# Pallette_v0_5.net
KiCad netlist of a schematic drawn in Altium Designer
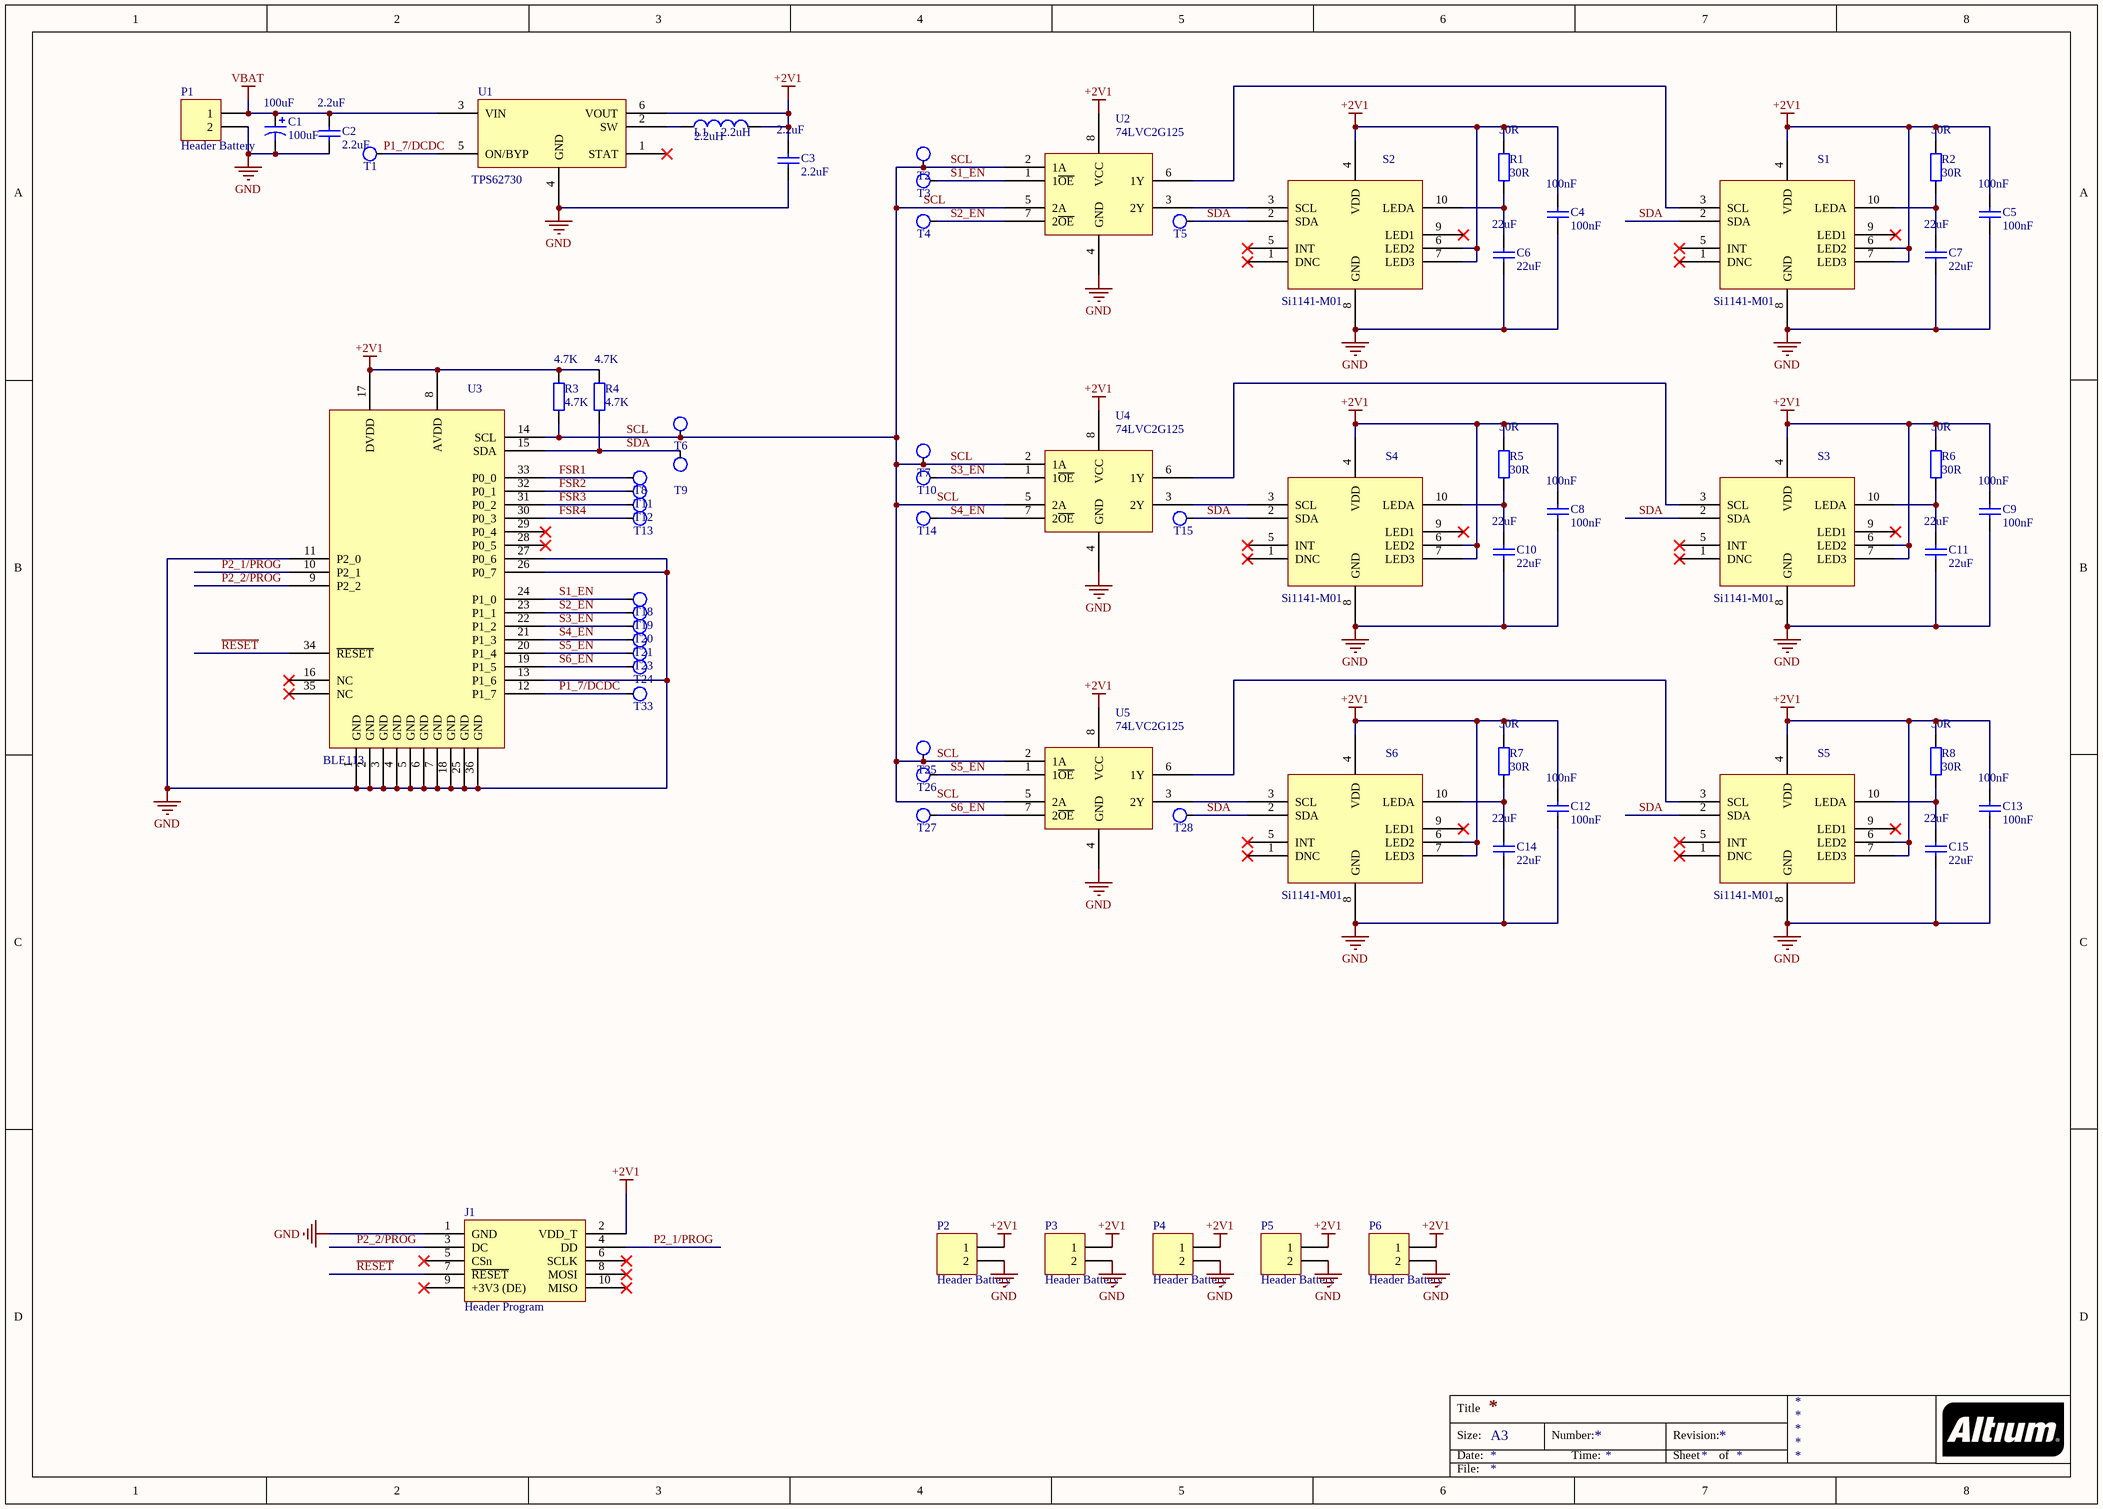
[diagram p0: Pallette v0.5.SchDoc]

(export (version "E")
  (design (tool "Eeschema 10.0.6"))
  (components
    (comp (ref "C1")
      (value "100uF")
      (footprint "1411")
      (description "CAP TANT POLY 100UF 8V 1411")
      (fields
        (field (name "ALTIUM_VALUE") "100uF")
        (field (name "DIGI-KEY PART NUMBER") "P16641CT-ND")
        (field (name "MANUFACTURER") "Panasonic Electronic Components")
      )
      (libsource (lib "Schlib") (part "Cap Pol 100uF"))
    )
    (comp (ref "C2")
      (value "2.2uF")
      (footprint "0402")
      (description "CAP CER 2.2UF 6.3V X5R 0402")
      (fields
        (field (name "ALTIUM_VALUE") "2.2uF")
        (field (name "DIGI-KEY PART NUMBER") "478-7885-1-ND")
        (field (name "MANUFACTURER PART NUMBER") "04026D225KAT2A")
      )
      (libsource (lib "Schlib") (part "Cap 2.2uF"))
    )
    (comp (ref "C3")
      (value "2.2uF")
      (footprint "0402")
      (description "CAP CER 2.2UF 6.3V X5R 0402")
      (fields
        (field (name "ALTIUM_VALUE") "2.2uF")
        (field (name "DIGI-KEY PART NUMBER") "478-7885-1-ND")
        (field (name "MANUFACTURER PART NUMBER") "04026D225KAT2A")
      )
      (libsource (lib "Schlib") (part "Cap 2.2uF"))
    )
    (comp (ref "C4")
      (value "100nF")
      (footprint "0402")
      (description "CAP CER 0.1UF 10V X5R 0402")
      (fields
        (field (name "ALTIUM_VALUE") "100nF")
        (field (name "DIGI-KEY PART NUMBER") "490-1318-1-ND")
        (field (name "MANUFACTURER") "Murata")
      )
      (libsource (lib "Schlib") (part "Cap 100nF"))
    )
    (comp (ref "C5")
      (value "100nF")
      (footprint "0402")
      (description "CAP CER 0.1UF 10V X5R 0402")
      (fields
        (field (name "ALTIUM_VALUE") "100nF")
        (field (name "DIGI-KEY PART NUMBER") "490-1318-1-ND")
        (field (name "MANUFACTURER") "Murata")
      )
      (libsource (lib "Schlib") (part "Cap 100nF"))
    )
    (comp (ref "C6")
      (value "22uF")
      (footprint "0603")
      (description "CAP CER 22UF 6.3V X5R 0603")
      (fields
        (field (name "ALTIUM_VALUE") "22uF")
        (field (name "DIGI-KEY PART NUMBER") "490-7611-1-ND")
        (field (name "MANUFACTURER PART NUMBER") "GRM188R60J226MEA0D")
      )
      (libsource (lib "Schlib") (part "Cap 22uF"))
    )
    (comp (ref "C7")
      (value "22uF")
      (footprint "0603")
      (description "CAP CER 22UF 6.3V X5R 0603")
      (fields
        (field (name "ALTIUM_VALUE") "22uF")
        (field (name "DIGI-KEY PART NUMBER") "490-7611-1-ND")
        (field (name "MANUFACTURER PART NUMBER") "GRM188R60J226MEA0D")
      )
      (libsource (lib "Schlib") (part "Cap 22uF"))
    )
    (comp (ref "C8")
      (value "100nF")
      (footprint "0402")
      (description "CAP CER 0.1UF 10V X5R 0402")
      (fields
        (field (name "ALTIUM_VALUE") "100nF")
        (field (name "DIGI-KEY PART NUMBER") "490-1318-1-ND")
        (field (name "MANUFACTURER") "Murata")
      )
      (libsource (lib "Schlib") (part "Cap 100nF"))
    )
    (comp (ref "C9")
      (value "100nF")
      (footprint "0402")
      (description "CAP CER 0.1UF 10V X5R 0402")
      (fields
        (field (name "ALTIUM_VALUE") "100nF")
        (field (name "DIGI-KEY PART NUMBER") "490-1318-1-ND")
        (field (name "MANUFACTURER") "Murata")
      )
      (libsource (lib "Schlib") (part "Cap 100nF"))
    )
    (comp (ref "C10")
      (value "22uF")
      (footprint "0603")
      (description "CAP CER 22UF 6.3V X5R 0603")
      (fields
        (field (name "ALTIUM_VALUE") "22uF")
        (field (name "DIGI-KEY PART NUMBER") "490-7611-1-ND")
        (field (name "MANUFACTURER PART NUMBER") "GRM188R60J226MEA0D")
      )
      (libsource (lib "Schlib") (part "Cap 22uF"))
    )
    (comp (ref "C11")
      (value "22uF")
      (footprint "0603")
      (description "CAP CER 22UF 6.3V X5R 0603")
      (fields
        (field (name "ALTIUM_VALUE") "22uF")
        (field (name "DIGI-KEY PART NUMBER") "490-7611-1-ND")
        (field (name "MANUFACTURER PART NUMBER") "GRM188R60J226MEA0D")
      )
      (libsource (lib "Schlib") (part "Cap 22uF"))
    )
    (comp (ref "C12")
      (value "100nF")
      (footprint "0402")
      (description "CAP CER 0.1UF 10V X5R 0402")
      (fields
        (field (name "ALTIUM_VALUE") "100nF")
        (field (name "DIGI-KEY PART NUMBER") "490-1318-1-ND")
        (field (name "MANUFACTURER") "Murata")
      )
      (libsource (lib "Schlib") (part "Cap 100nF"))
    )
    (comp (ref "C13")
      (value "100nF")
      (footprint "0402")
      (description "CAP CER 0.1UF 10V X5R 0402")
      (fields
        (field (name "ALTIUM_VALUE") "100nF")
        (field (name "DIGI-KEY PART NUMBER") "490-1318-1-ND")
        (field (name "MANUFACTURER") "Murata")
      )
      (libsource (lib "Schlib") (part "Cap 100nF"))
    )
    (comp (ref "C14")
      (value "22uF")
      (footprint "0603")
      (description "CAP CER 22UF 6.3V X5R 0603")
      (fields
        (field (name "ALTIUM_VALUE") "22uF")
        (field (name "DIGI-KEY PART NUMBER") "490-7611-1-ND")
        (field (name "MANUFACTURER PART NUMBER") "GRM188R60J226MEA0D")
      )
      (libsource (lib "Schlib") (part "Cap 22uF"))
    )
    (comp (ref "C15")
      (value "22uF")
      (footprint "0603")
      (description "CAP CER 22UF 6.3V X5R 0603")
      (fields
        (field (name "ALTIUM_VALUE") "22uF")
        (field (name "DIGI-KEY PART NUMBER") "490-7611-1-ND")
        (field (name "MANUFACTURER PART NUMBER") "GRM188R60J226MEA0D")
      )
      (libsource (lib "Schlib") (part "Cap 22uF"))
    )
    (comp (ref "J1")
      (value "Header Program")
      (footprint "TC2050-IDC-NL")
      (description "PADS PROGRAMMING")
      (libsource (lib "Schlib") (part "Header Program"))
    )
    (comp (ref "L1")
      (value "2.2uH")
      (footprint "0805")
      (description "FIXED IND 2.2UH 800MA 120 MOHM")
      (fields
        (field (name "ALTIUM_VALUE") "2.2uH")
        (field (name "DIGI-KEY PART NUMBER") "445-6758-1-ND")
        (field (name "MANUFACTURER") "TDK Corporation")
      )
      (libsource (lib "Schlib") (part "Ind 2.2uH"))
    )
    (comp (ref "P1")
      (value "Header Battery")
      (footprint "Battery Leads")
      (description "PADS BATTERY")
      (fields (field (name "PUBLISHER") "Altium Limited"))
      (libsource (lib "Schlib") (part "Header Battery"))
    )
    (comp (ref "P2")
      (value "Header Battery")
      (footprint "Battery Leads")
      (description "PADS BATTERY")
      (fields (field (name "PUBLISHER") "Altium Limited"))
      (libsource (lib "Schlib") (part "Header Battery"))
    )
    (comp (ref "P3")
      (value "Header Battery")
      (footprint "Battery Leads")
      (description "PADS BATTERY")
      (fields (field (name "PUBLISHER") "Altium Limited"))
      (libsource (lib "Schlib") (part "Header Battery"))
    )
    (comp (ref "P4")
      (value "Header Battery")
      (footprint "Battery Leads")
      (description "PADS BATTERY")
      (fields (field (name "PUBLISHER") "Altium Limited"))
      (libsource (lib "Schlib") (part "Header Battery"))
    )
    (comp (ref "P5")
      (value "Header Battery")
      (footprint "Battery Leads")
      (description "PADS BATTERY")
      (fields (field (name "PUBLISHER") "Altium Limited"))
      (libsource (lib "Schlib") (part "Header Battery"))
    )
    (comp (ref "P6")
      (value "Header Battery")
      (footprint "Battery Leads")
      (description "PADS BATTERY")
      (fields (field (name "PUBLISHER") "Altium Limited"))
      (libsource (lib "Schlib") (part "Header Battery"))
    )
    (comp (ref "R1")
      (value "30R")
      (footprint "0402")
      (description "RES SMD 30 OHM 1% 1/16W 0402")
      (fields
        (field (name "ALTIUM_VALUE") "30R")
        (field (name "DIGI-KEY PART NUMBER") "311-30LRCT-ND")
        (field (name "MANUFACTURER") "Yageo")
      )
      (libsource (lib "Schlib") (part "Res 30R"))
    )
    (comp (ref "R2")
      (value "30R")
      (footprint "0402")
      (description "RES SMD 30 OHM 1% 1/16W 0402")
      (fields
        (field (name "ALTIUM_VALUE") "30R")
        (field (name "DIGI-KEY PART NUMBER") "311-30LRCT-ND")
        (field (name "MANUFACTURER") "Yageo")
      )
      (libsource (lib "Schlib") (part "Res 30R"))
    )
    (comp (ref "R3")
      (value "4.7K")
      (footprint "0402")
      (description "RES SMD 4.7K OHM 1% 1/16W 0402")
      (fields
        (field (name "ALTIUM_VALUE") "4.7K")
        (field (name "DIGI-KEY PART NUMBER") "311-4.7KLRCT-ND")
        (field (name "MANUFACTURER") "Yageo")
      )
      (libsource (lib "Schlib") (part "Res 4.7K"))
    )
    (comp (ref "R4")
      (value "4.7K")
      (footprint "0402")
      (description "RES SMD 4.7K OHM 1% 1/16W 0402")
      (fields
        (field (name "ALTIUM_VALUE") "4.7K")
        (field (name "DIGI-KEY PART NUMBER") "311-4.7KLRCT-ND")
        (field (name "MANUFACTURER") "Yageo")
      )
      (libsource (lib "Schlib") (part "Res 4.7K"))
    )
    (comp (ref "R5")
      (value "30R")
      (footprint "0402")
      (description "RES SMD 30 OHM 1% 1/16W 0402")
      (fields
        (field (name "ALTIUM_VALUE") "30R")
        (field (name "DIGI-KEY PART NUMBER") "311-30LRCT-ND")
        (field (name "MANUFACTURER") "Yageo")
      )
      (libsource (lib "Schlib") (part "Res 30R"))
    )
    (comp (ref "R6")
      (value "30R")
      (footprint "0402")
      (description "RES SMD 30 OHM 1% 1/16W 0402")
      (fields
        (field (name "ALTIUM_VALUE") "30R")
        (field (name "DIGI-KEY PART NUMBER") "311-30LRCT-ND")
        (field (name "MANUFACTURER") "Yageo")
      )
      (libsource (lib "Schlib") (part "Res 30R"))
    )
    (comp (ref "R7")
      (value "30R")
      (footprint "0402")
      (description "RES SMD 30 OHM 1% 1/16W 0402")
      (fields
        (field (name "ALTIUM_VALUE") "30R")
        (field (name "DIGI-KEY PART NUMBER") "311-30LRCT-ND")
        (field (name "MANUFACTURER") "Yageo")
      )
      (libsource (lib "Schlib") (part "Res 30R"))
    )
    (comp (ref "R8")
      (value "30R")
      (footprint "0402")
      (description "RES SMD 30 OHM 1% 1/16W 0402")
      (fields
        (field (name "ALTIUM_VALUE") "30R")
        (field (name "DIGI-KEY PART NUMBER") "311-30LRCT-ND")
        (field (name "MANUFACTURER") "Yageo")
      )
      (libsource (lib "Schlib") (part "Res 30R"))
    )
    (comp (ref "S1")
      (value "Si1141-M01")
      (footprint "SI1141-M01")
      (description "SENSOR IR PROXIMITY AMB LT 10QFN")
      (fields
        (field (name "DIGI-KEY PART NUMBER") "336-3260-1-ND")
        (field (name "MANUFACTURER") "Silicon Labs")
      )
      (libsource (lib "Schlib") (part "Si1141-M01"))
    )
    (comp (ref "S2")
      (value "Si1141-M01")
      (footprint "SI1141-M01")
      (description "SENSOR IR PROXIMITY AMB LT 10QFN")
      (fields
        (field (name "DIGI-KEY PART NUMBER") "336-3260-1-ND")
        (field (name "MANUFACTURER") "Silicon Labs")
      )
      (libsource (lib "Schlib") (part "Si1141-M01"))
    )
    (comp (ref "S3")
      (value "Si1141-M01")
      (footprint "SI1141-M01")
      (description "SENSOR IR PROXIMITY AMB LT 10QFN")
      (fields
        (field (name "DIGI-KEY PART NUMBER") "336-3260-1-ND")
        (field (name "MANUFACTURER") "Silicon Labs")
      )
      (libsource (lib "Schlib") (part "Si1141-M01"))
    )
    (comp (ref "S4")
      (value "Si1141-M01")
      (footprint "SI1141-M01")
      (description "SENSOR IR PROXIMITY AMB LT 10QFN")
      (fields
        (field (name "DIGI-KEY PART NUMBER") "336-3260-1-ND")
        (field (name "MANUFACTURER") "Silicon Labs")
      )
      (libsource (lib "Schlib") (part "Si1141-M01"))
    )
    (comp (ref "S5")
      (value "Si1141-M01")
      (footprint "SI1141-M01")
      (description "SENSOR IR PROXIMITY AMB LT 10QFN")
      (fields
        (field (name "DIGI-KEY PART NUMBER") "336-3260-1-ND")
        (field (name "MANUFACTURER") "Silicon Labs")
      )
      (libsource (lib "Schlib") (part "Si1141-M01"))
    )
    (comp (ref "S6")
      (value "Si1141-M01")
      (footprint "SI1141-M01")
      (description "SENSOR IR PROXIMITY AMB LT 10QFN")
      (fields
        (field (name "DIGI-KEY PART NUMBER") "336-3260-1-ND")
        (field (name "MANUFACTURER") "Silicon Labs")
      )
      (libsource (lib "Schlib") (part "Si1141-M01"))
    )
    (comp (ref "T1")
      (value "TP 1.2X2MM")
      (footprint "TP 1.2x2MM")
      (description "TEST POINT")
      (libsource (lib "Schlib") (part "TP 1.2X2MM"))
    )
    (comp (ref "T2")
      (value "TP 1.2X2MM")
      (footprint "TP 1.2x2MM")
      (description "TEST POINT")
      (libsource (lib "Schlib") (part "TP 1.2X2MM"))
    )
    (comp (ref "T3")
      (value "TP 1.2X2MM")
      (footprint "TP 1.2x2MM")
      (description "TEST POINT")
      (libsource (lib "Schlib") (part "TP 1.2X2MM"))
    )
    (comp (ref "T4")
      (value "TP 1.2X2MM")
      (footprint "TP 1.2x2MM")
      (description "TEST POINT")
      (libsource (lib "Schlib") (part "TP 1.2X2MM"))
    )
    (comp (ref "T5")
      (value "TP 1.2X2MM")
      (footprint "TP 1.2x2MM")
      (description "TEST POINT")
      (libsource (lib "Schlib") (part "TP 1.2X2MM"))
    )
    (comp (ref "T6")
      (value "TP 1.2X2MM")
      (footprint "TP 1.2x2MM")
      (description "TEST POINT")
      (libsource (lib "Schlib") (part "TP 1.2X2MM"))
    )
    (comp (ref "T7")
      (value "TP 1.2X2MM")
      (footprint "TP 1.2x2MM")
      (description "TEST POINT")
      (libsource (lib "Schlib") (part "TP 1.2X2MM"))
    )
    (comp (ref "T8")
      (value "TP 1.2X2MM")
      (footprint "TP 1.2x2MM")
      (description "TEST POINT")
      (libsource (lib "Schlib") (part "TP 1.2X2MM"))
    )
    (comp (ref "T9")
      (value "TP 1.2X2MM")
      (footprint "TP 1.2x2MM")
      (description "TEST POINT")
      (libsource (lib "Schlib") (part "TP 1.2X2MM"))
    )
    (comp (ref "T10")
      (value "TP 1.2X2MM")
      (footprint "TP 1.2x2MM")
      (description "TEST POINT")
      (libsource (lib "Schlib") (part "TP 1.2X2MM"))
    )
    (comp (ref "T11")
      (value "TP 1.2X2MM")
      (footprint "TP 1.2x2MM")
      (description "TEST POINT")
      (libsource (lib "Schlib") (part "TP 1.2X2MM"))
    )
    (comp (ref "T12")
      (value "TP 1.2X2MM")
      (footprint "TP 1.2x2MM")
      (description "TEST POINT")
      (libsource (lib "Schlib") (part "TP 1.2X2MM"))
    )
    (comp (ref "T13")
      (value "TP 1.2X2MM")
      (footprint "TP 1.2x2MM")
      (description "TEST POINT")
      (libsource (lib "Schlib") (part "TP 1.2X2MM"))
    )
    (comp (ref "T14")
      (value "TP 1.2X2MM")
      (footprint "TP 1.2x2MM")
      (description "TEST POINT")
      (libsource (lib "Schlib") (part "TP 1.2X2MM"))
    )
    (comp (ref "T15")
      (value "TP 1.2X2MM")
      (footprint "TP 1.2x2MM")
      (description "TEST POINT")
      (libsource (lib "Schlib") (part "TP 1.2X2MM"))
    )
    (comp (ref "T18")
      (value "TP 1.2X2MM")
      (footprint "TP 1.2x2MM")
      (description "TEST POINT")
      (libsource (lib "Schlib") (part "TP 1.2X2MM"))
    )
    (comp (ref "T19")
      (value "TP 1.2X2MM")
      (footprint "TP 1.2x2MM")
      (description "TEST POINT")
      (libsource (lib "Schlib") (part "TP 1.2X2MM"))
    )
    (comp (ref "T20")
      (value "TP 1.2X2MM")
      (footprint "TP 1.2x2MM")
      (description "TEST POINT")
      (libsource (lib "Schlib") (part "TP 1.2X2MM"))
    )
    (comp (ref "T21")
      (value "TP 1.2X2MM")
      (footprint "TP 1.2x2MM")
      (description "TEST POINT")
      (libsource (lib "Schlib") (part "TP 1.2X2MM"))
    )
    (comp (ref "T23")
      (value "TP 1.2X2MM")
      (footprint "TP 1.2x2MM")
      (description "TEST POINT")
      (libsource (lib "Schlib") (part "TP 1.2X2MM"))
    )
    (comp (ref "T24")
      (value "TP 1.2X2MM")
      (footprint "TP 1.2x2MM")
      (description "TEST POINT")
      (libsource (lib "Schlib") (part "TP 1.2X2MM"))
    )
    (comp (ref "T25")
      (value "TP 1.2X2MM")
      (footprint "TP 1.2x2MM")
      (description "TEST POINT")
      (libsource (lib "Schlib") (part "TP 1.2X2MM"))
    )
    (comp (ref "T26")
      (value "TP 1.2X2MM")
      (footprint "TP 1.2x2MM")
      (description "TEST POINT")
      (libsource (lib "Schlib") (part "TP 1.2X2MM"))
    )
    (comp (ref "T27")
      (value "TP 1.2X2MM")
      (footprint "TP 1.2x2MM")
      (description "TEST POINT")
      (libsource (lib "Schlib") (part "TP 1.2X2MM"))
    )
    (comp (ref "T28")
      (value "TP 1.2X2MM")
      (footprint "TP 1.2x2MM")
      (description "TEST POINT")
      (libsource (lib "Schlib") (part "TP 1.2X2MM"))
    )
    (comp (ref "T33")
      (value "TP 1.2X2MM")
      (footprint "TP 1.2x2MM")
      (description "TEST POINT")
      (libsource (lib "Schlib") (part "TP 1.2X2MM"))
    )
    (comp (ref "U1")
      (value "TPS62730")
      (footprint "6-UFDFN")
      (description "IC DCDC CONV STP-DN SYNC LP 6SON")
      (fields
        (field (name "DIGI-KEY PART NUMBER") "296-28820-1-ND")
        (field (name "MANUFACTURER") "Texas Instruments")
      )
      (libsource (lib "Schlib") (part "TPS62730"))
    )
    (comp (ref "U2")
      (value "74LVC2G125")
      (footprint "VSSOP8")
      (description "IC BUS BUFF DVR TRI-ST DL 8VSSOP")
      (fields
        (field (name "MANUFACTURER") "NXP Semiconductors")
        (field (name "MANUFACTURER PART NUMBER") "74LVC2G125DC,125")
      )
      (libsource (lib "Schlib") (part "74LVC2G125"))
    )
    (comp (ref "U3")
      (value "BLE113")
      (footprint "BLE113-A")
      (description "MODULE BT 4.0 BLE113 OTA")
      (fields
        (field (name "MANUFACTURER") "Silicon Labs")
        (field (name "MANUFACTURER PART NUMBER") "BLE113-A-M256K")
      )
      (libsource (lib "Schlib") (part "BLE113"))
    )
    (comp (ref "U4")
      (value "74LVC2G125")
      (footprint "VSSOP8")
      (description "IC BUS BUFF DVR TRI-ST DL 8VSSOP")
      (fields
        (field (name "MANUFACTURER") "NXP Semiconductors")
        (field (name "MANUFACTURER PART NUMBER") "74LVC2G125DC,125")
      )
      (libsource (lib "Schlib") (part "74LVC2G125"))
    )
    (comp (ref "U5")
      (value "74LVC2G125")
      (footprint "VSSOP8")
      (description "IC BUS BUFF DVR TRI-ST DL 8VSSOP")
      (fields
        (field (name "MANUFACTURER") "NXP Semiconductors")
        (field (name "MANUFACTURER PART NUMBER") "74LVC2G125DC,125")
      )
      (libsource (lib "Schlib") (part "74LVC2G125"))
    )
  )
  (nets
    (net (code "1") (name "+2V1") (class "Default")
      (node (ref "C12") (pin "2") (pinfunction "2_2") (pintype "passive"))
      (node (ref "C13") (pin "2") (pinfunction "2_2") (pintype "passive"))
      (node (ref "C3") (pin "2") (pinfunction "2_2") (pintype "passive"))
      (node (ref "C4") (pin "2") (pinfunction "2_2") (pintype "passive"))
      (node (ref "C5") (pin "2") (pinfunction "2_2") (pintype "passive"))
      (node (ref "C8") (pin "2") (pinfunction "2_2") (pintype "passive"))
      (node (ref "C9") (pin "2") (pinfunction "2_2") (pintype "passive"))
      (node (ref "J1") (pin "2") (pinfunction "VDD_T_2") (pintype "passive"))
      (node (ref "L1") (pin "2") (pinfunction "2_2") (pintype "passive"))
      (node (ref "P2") (pin "1") (pinfunction "1_1") (pintype "passive"))
      (node (ref "P3") (pin "1") (pinfunction "1_1") (pintype "passive"))
      (node (ref "P4") (pin "1") (pinfunction "1_1") (pintype "passive"))
      (node (ref "P5") (pin "1") (pinfunction "1_1") (pintype "passive"))
      (node (ref "P6") (pin "1") (pinfunction "1_1") (pintype "passive"))
      (node (ref "R1") (pin "2") (pinfunction "2_2") (pintype "passive"))
      (node (ref "R2") (pin "2") (pinfunction "2_2") (pintype "passive"))
      (node (ref "R3") (pin "2") (pinfunction "2_2") (pintype "passive"))
      (node (ref "R4") (pin "2") (pinfunction "2_2") (pintype "passive"))
      (node (ref "R5") (pin "2") (pinfunction "2_2") (pintype "passive"))
      (node (ref "R6") (pin "2") (pinfunction "2_2") (pintype "passive"))
      (node (ref "R7") (pin "2") (pinfunction "2_2") (pintype "passive"))
      (node (ref "R8") (pin "2") (pinfunction "2_2") (pintype "passive"))
      (node (ref "S1") (pin "4") (pinfunction "VDD_4") (pintype "passive"))
      (node (ref "S1") (pin "6") (pinfunction "LED2_6") (pintype "passive"))
      (node (ref "S1") (pin "7") (pinfunction "LED3_7") (pintype "passive"))
      (node (ref "S2") (pin "4") (pinfunction "VDD_4") (pintype "passive"))
      (node (ref "S2") (pin "6") (pinfunction "LED2_6") (pintype "passive"))
      (node (ref "S2") (pin "7") (pinfunction "LED3_7") (pintype "passive"))
      (node (ref "S3") (pin "4") (pinfunction "VDD_4") (pintype "passive"))
      (node (ref "S3") (pin "6") (pinfunction "LED2_6") (pintype "passive"))
      (node (ref "S3") (pin "7") (pinfunction "LED3_7") (pintype "passive"))
      (node (ref "S4") (pin "4") (pinfunction "VDD_4") (pintype "passive"))
      (node (ref "S4") (pin "6") (pinfunction "LED2_6") (pintype "passive"))
      (node (ref "S4") (pin "7") (pinfunction "LED3_7") (pintype "passive"))
      (node (ref "S5") (pin "4") (pinfunction "VDD_4") (pintype "passive"))
      (node (ref "S5") (pin "6") (pinfunction "LED2_6") (pintype "passive"))
      (node (ref "S5") (pin "7") (pinfunction "LED3_7") (pintype "passive"))
      (node (ref "S6") (pin "4") (pinfunction "VDD_4") (pintype "passive"))
      (node (ref "S6") (pin "6") (pinfunction "LED2_6") (pintype "passive"))
      (node (ref "S6") (pin "7") (pinfunction "LED3_7") (pintype "passive"))
      (node (ref "U1") (pin "6") (pinfunction "VOUT_6") (pintype "passive"))
      (node (ref "U2") (pin "8") (pinfunction "VCC_8") (pintype "passive"))
      (node (ref "U3") (pin "17") (pinfunction "DVDD_17") (pintype "passive"))
      (node (ref "U3") (pin "8") (pinfunction "AVDD_8") (pintype "passive"))
      (node (ref "U4") (pin "8") (pinfunction "VCC_8") (pintype "passive"))
      (node (ref "U5") (pin "8") (pinfunction "VCC_8") (pintype "passive"))
    )
    (net (code "2") (name "/FSR1") (class "Default")
      (node (ref "T8") (pin "1") (pintype "passive"))
      (node (ref "U3") (pin "33") (pinfunction "P0_0_33") (pintype "passive"))
    )
    (net (code "3") (name "/FSR2") (class "Default")
      (node (ref "T11") (pin "1") (pintype "passive"))
      (node (ref "U3") (pin "32") (pinfunction "P0_1_32") (pintype "passive"))
    )
    (net (code "4") (name "/FSR3") (class "Default")
      (node (ref "T12") (pin "1") (pintype "passive"))
      (node (ref "U3") (pin "31") (pinfunction "P0_2_31") (pintype "passive"))
    )
    (net (code "5") (name "/FSR4") (class "Default")
      (node (ref "T13") (pin "1") (pintype "passive"))
      (node (ref "U3") (pin "30") (pinfunction "P0_3_30") (pintype "passive"))
    )
    (net (code "6") (name "/P1_7{slash}DCDC") (class "Default")
      (node (ref "T1") (pin "1") (pintype "passive"))
      (node (ref "T33") (pin "1") (pintype "passive"))
      (node (ref "U1") (pin "5") (pinfunction "ON/BYP_5") (pintype "passive"))
      (node (ref "U3") (pin "12") (pinfunction "P1_7_12") (pintype "passive"))
    )
    (net (code "7") (name "/P2_1{slash}PROG") (class "Default")
      (node (ref "J1") (pin "4") (pinfunction "DD_4") (pintype "passive"))
      (node (ref "U3") (pin "10") (pinfunction "P2_1_10") (pintype "passive"))
    )
    (net (code "8") (name "/P2_2{slash}PROG") (class "Default")
      (node (ref "J1") (pin "3") (pinfunction "DC_3") (pintype "passive"))
      (node (ref "U3") (pin "9") (pinfunction "P2_2_9") (pintype "passive"))
    )
    (net (code "9") (name "/S1_EN") (class "Default")
      (node (ref "T18") (pin "1") (pintype "passive"))
      (node (ref "T3") (pin "1") (pintype "passive"))
      (node (ref "U2") (pin "1") (pinfunction "1~{OE}_1") (pintype "passive"))
      (node (ref "U3") (pin "24") (pinfunction "P1_0_24") (pintype "passive"))
    )
    (net (code "10") (name "/S2_EN") (class "Default")
      (node (ref "T19") (pin "1") (pintype "passive"))
      (node (ref "T4") (pin "1") (pintype "passive"))
      (node (ref "U2") (pin "7") (pinfunction "2~{OE}_7") (pintype "passive"))
      (node (ref "U3") (pin "23") (pinfunction "P1_1_23") (pintype "passive"))
    )
    (net (code "11") (name "/S3_EN") (class "Default")
      (node (ref "T10") (pin "1") (pintype "passive"))
      (node (ref "T20") (pin "1") (pintype "passive"))
      (node (ref "U3") (pin "22") (pinfunction "P1_2_22") (pintype "passive"))
      (node (ref "U4") (pin "1") (pinfunction "1~{OE}_1") (pintype "passive"))
    )
    (net (code "12") (name "/S4_EN") (class "Default")
      (node (ref "T14") (pin "1") (pintype "passive"))
      (node (ref "T21") (pin "1") (pintype "passive"))
      (node (ref "U3") (pin "21") (pinfunction "P1_3_21") (pintype "passive"))
      (node (ref "U4") (pin "7") (pinfunction "2~{OE}_7") (pintype "passive"))
    )
    (net (code "13") (name "/S5_EN") (class "Default")
      (node (ref "T23") (pin "1") (pintype "passive"))
      (node (ref "T26") (pin "1") (pintype "passive"))
      (node (ref "U3") (pin "20") (pinfunction "P1_4_20") (pintype "passive"))
      (node (ref "U5") (pin "1") (pinfunction "1~{OE}_1") (pintype "passive"))
    )
    (net (code "14") (name "/S6_EN") (class "Default")
      (node (ref "T24") (pin "1") (pintype "passive"))
      (node (ref "T27") (pin "1") (pintype "passive"))
      (node (ref "U3") (pin "19") (pinfunction "P1_5_19") (pintype "passive"))
      (node (ref "U5") (pin "7") (pinfunction "2~{OE}_7") (pintype "passive"))
    )
    (net (code "15") (name "/SCL") (class "Default")
      (node (ref "R3") (pin "1") (pinfunction "1_1") (pintype "passive"))
      (node (ref "T2") (pin "1") (pintype "passive"))
      (node (ref "T25") (pin "1") (pintype "passive"))
      (node (ref "T6") (pin "1") (pintype "passive"))
      (node (ref "T7") (pin "1") (pintype "passive"))
      (node (ref "U2") (pin "2") (pinfunction "1A_2") (pintype "passive"))
      (node (ref "U2") (pin "5") (pinfunction "2A_5") (pintype "passive"))
      (node (ref "U3") (pin "14") (pinfunction "SCL_14") (pintype "passive"))
      (node (ref "U4") (pin "2") (pinfunction "1A_2") (pintype "passive"))
      (node (ref "U4") (pin "5") (pinfunction "2A_5") (pintype "passive"))
      (node (ref "U5") (pin "2") (pinfunction "1A_2") (pintype "passive"))
      (node (ref "U5") (pin "5") (pinfunction "2A_5") (pintype "passive"))
    )
    (net (code "16") (name "/SDA") (class "Default")
      (node (ref "R4") (pin "1") (pinfunction "1_1") (pintype "passive"))
      (node (ref "S1") (pin "2") (pinfunction "SDA_2") (pintype "passive"))
      (node (ref "S2") (pin "2") (pinfunction "SDA_2") (pintype "passive"))
      (node (ref "S3") (pin "2") (pinfunction "SDA_2") (pintype "passive"))
      (node (ref "S4") (pin "2") (pinfunction "SDA_2") (pintype "passive"))
      (node (ref "S5") (pin "2") (pinfunction "SDA_2") (pintype "passive"))
      (node (ref "S6") (pin "2") (pinfunction "SDA_2") (pintype "passive"))
      (node (ref "T15") (pin "1") (pintype "passive"))
      (node (ref "T28") (pin "1") (pintype "passive"))
      (node (ref "T5") (pin "1") (pintype "passive"))
      (node (ref "T9") (pin "1") (pintype "passive"))
      (node (ref "U3") (pin "15") (pinfunction "SDA_15") (pintype "passive"))
    )
    (net (code "17") (name "/~{RESET}") (class "Default")
      (node (ref "J1") (pin "7") (pinfunction "~{RESET}_7") (pintype "passive"))
      (node (ref "U3") (pin "34") (pinfunction "~{RESET}_34") (pintype "passive"))
    )
    (net (code "18") (name "GND") (class "Default")
      (node (ref "C1") (pin "2") (pinfunction "2_2") (pintype "passive"))
      (node (ref "C10") (pin "1") (pinfunction "1_1") (pintype "passive"))
      (node (ref "C11") (pin "1") (pinfunction "1_1") (pintype "passive"))
      (node (ref "C12") (pin "1") (pinfunction "1_1") (pintype "passive"))
      (node (ref "C13") (pin "1") (pinfunction "1_1") (pintype "passive"))
      (node (ref "C14") (pin "1") (pinfunction "1_1") (pintype "passive"))
      (node (ref "C15") (pin "1") (pinfunction "1_1") (pintype "passive"))
      (node (ref "C2") (pin "1") (pinfunction "1_1") (pintype "passive"))
      (node (ref "C3") (pin "1") (pinfunction "1_1") (pintype "passive"))
      (node (ref "C4") (pin "1") (pinfunction "1_1") (pintype "passive"))
      (node (ref "C5") (pin "1") (pinfunction "1_1") (pintype "passive"))
      (node (ref "C6") (pin "1") (pinfunction "1_1") (pintype "passive"))
      (node (ref "C7") (pin "1") (pinfunction "1_1") (pintype "passive"))
      (node (ref "C8") (pin "1") (pinfunction "1_1") (pintype "passive"))
      (node (ref "C9") (pin "1") (pinfunction "1_1") (pintype "passive"))
      (node (ref "J1") (pin "1") (pinfunction "GND_1") (pintype "passive"))
      (node (ref "P1") (pin "2") (pinfunction "2_2") (pintype "passive"))
      (node (ref "P2") (pin "2") (pinfunction "2_2") (pintype "passive"))
      (node (ref "P3") (pin "2") (pinfunction "2_2") (pintype "passive"))
      (node (ref "P4") (pin "2") (pinfunction "2_2") (pintype "passive"))
      (node (ref "P5") (pin "2") (pinfunction "2_2") (pintype "passive"))
      (node (ref "P6") (pin "2") (pinfunction "2_2") (pintype "passive"))
      (node (ref "S1") (pin "8") (pinfunction "GND_8") (pintype "passive"))
      (node (ref "S2") (pin "8") (pinfunction "GND_8") (pintype "passive"))
      (node (ref "S3") (pin "8") (pinfunction "GND_8") (pintype "passive"))
      (node (ref "S4") (pin "8") (pinfunction "GND_8") (pintype "passive"))
      (node (ref "S5") (pin "8") (pinfunction "GND_8") (pintype "passive"))
      (node (ref "S6") (pin "8") (pinfunction "GND_8") (pintype "passive"))
      (node (ref "U1") (pin "4") (pinfunction "GND_4") (pintype "passive"))
      (node (ref "U2") (pin "4") (pinfunction "GND_4") (pintype "passive"))
      (node (ref "U3") (pin "1") (pinfunction "GND_1") (pintype "passive"))
      (node (ref "U3") (pin "11") (pinfunction "P2_0_11") (pintype "passive"))
      (node (ref "U3") (pin "13") (pinfunction "P1_6_13") (pintype "passive"))
      (node (ref "U3") (pin "18") (pinfunction "GND_18") (pintype "passive"))
      (node (ref "U3") (pin "2") (pinfunction "GND_2") (pintype "passive"))
      (node (ref "U3") (pin "25") (pinfunction "GND_25") (pintype "passive"))
      (node (ref "U3") (pin "26") (pinfunction "P0_7_26") (pintype "passive"))
      (node (ref "U3") (pin "27") (pinfunction "P0_6_27") (pintype "passive"))
      (node (ref "U3") (pin "3") (pinfunction "GND_3") (pintype "passive"))
      (node (ref "U3") (pin "36") (pinfunction "GND_36") (pintype "passive"))
      (node (ref "U3") (pin "4") (pinfunction "GND_4") (pintype "passive"))
      (node (ref "U3") (pin "5") (pinfunction "GND_5") (pintype "passive"))
      (node (ref "U3") (pin "6") (pinfunction "GND_6") (pintype "passive"))
      (node (ref "U3") (pin "7") (pinfunction "GND_7") (pintype "passive"))
      (node (ref "U4") (pin "4") (pinfunction "GND_4") (pintype "passive"))
      (node (ref "U5") (pin "4") (pinfunction "GND_4") (pintype "passive"))
    )
    (net (code "19") (name "Net-(S1-LEDA)") (class "Default")
      (node (ref "C7") (pin "2") (pinfunction "2_2") (pintype "passive"))
      (node (ref "R2") (pin "1") (pinfunction "1_1") (pintype "passive"))
      (node (ref "S1") (pin "10") (pinfunction "LEDA_10") (pintype "passive"))
    )
    (net (code "20") (name "Net-(S1-SCL)") (class "Default")
      (node (ref "S1") (pin "3") (pinfunction "SCL_3") (pintype "passive"))
      (node (ref "U2") (pin "6") (pinfunction "1Y_6") (pintype "passive"))
    )
    (net (code "21") (name "Net-(S2-LEDA)") (class "Default")
      (node (ref "C6") (pin "2") (pinfunction "2_2") (pintype "passive"))
      (node (ref "R1") (pin "1") (pinfunction "1_1") (pintype "passive"))
      (node (ref "S2") (pin "10") (pinfunction "LEDA_10") (pintype "passive"))
    )
    (net (code "22") (name "Net-(S2-SCL)") (class "Default")
      (node (ref "S2") (pin "3") (pinfunction "SCL_3") (pintype "passive"))
      (node (ref "U2") (pin "3") (pinfunction "2Y_3") (pintype "passive"))
    )
    (net (code "23") (name "Net-(S3-LEDA)") (class "Default")
      (node (ref "C11") (pin "2") (pinfunction "2_2") (pintype "passive"))
      (node (ref "R6") (pin "1") (pinfunction "1_1") (pintype "passive"))
      (node (ref "S3") (pin "10") (pinfunction "LEDA_10") (pintype "passive"))
    )
    (net (code "24") (name "Net-(S3-SCL)") (class "Default")
      (node (ref "S3") (pin "3") (pinfunction "SCL_3") (pintype "passive"))
      (node (ref "U4") (pin "6") (pinfunction "1Y_6") (pintype "passive"))
    )
    (net (code "25") (name "Net-(S4-LEDA)") (class "Default")
      (node (ref "C10") (pin "2") (pinfunction "2_2") (pintype "passive"))
      (node (ref "R5") (pin "1") (pinfunction "1_1") (pintype "passive"))
      (node (ref "S4") (pin "10") (pinfunction "LEDA_10") (pintype "passive"))
    )
    (net (code "26") (name "Net-(S4-SCL)") (class "Default")
      (node (ref "S4") (pin "3") (pinfunction "SCL_3") (pintype "passive"))
      (node (ref "U4") (pin "3") (pinfunction "2Y_3") (pintype "passive"))
    )
    (net (code "27") (name "Net-(S5-LEDA)") (class "Default")
      (node (ref "C15") (pin "2") (pinfunction "2_2") (pintype "passive"))
      (node (ref "R8") (pin "1") (pinfunction "1_1") (pintype "passive"))
      (node (ref "S5") (pin "10") (pinfunction "LEDA_10") (pintype "passive"))
    )
    (net (code "28") (name "Net-(S5-SCL)") (class "Default")
      (node (ref "S5") (pin "3") (pinfunction "SCL_3") (pintype "passive"))
      (node (ref "U5") (pin "6") (pinfunction "1Y_6") (pintype "passive"))
    )
    (net (code "29") (name "Net-(S6-LEDA)") (class "Default")
      (node (ref "C14") (pin "2") (pinfunction "2_2") (pintype "passive"))
      (node (ref "R7") (pin "1") (pinfunction "1_1") (pintype "passive"))
      (node (ref "S6") (pin "10") (pinfunction "LEDA_10") (pintype "passive"))
    )
    (net (code "30") (name "Net-(S6-SCL)") (class "Default")
      (node (ref "S6") (pin "3") (pinfunction "SCL_3") (pintype "passive"))
      (node (ref "U5") (pin "3") (pinfunction "2Y_3") (pintype "passive"))
    )
    (net (code "31") (name "Net-(U1-SW)") (class "Default")
      (node (ref "L1") (pin "1") (pinfunction "1_1") (pintype "passive"))
      (node (ref "U1") (pin "2") (pinfunction "SW_2") (pintype "passive"))
    )
    (net (code "32") (name "VBAT") (class "Default")
      (node (ref "C1") (pin "1") (pinfunction "1_1") (pintype "passive"))
      (node (ref "C2") (pin "2") (pinfunction "2_2") (pintype "passive"))
      (node (ref "P1") (pin "1") (pinfunction "1_1") (pintype "passive"))
      (node (ref "U1") (pin "3") (pinfunction "VIN_3") (pintype "passive"))
    )
    (net (code "33") (name "unconnected-(J1-+3V3_(DE)-Pad9)") (class "Default")
      (node (ref "J1") (pin "9") (pinfunction "+3V3_(DE)_9") (pintype "passive+no_connect"))
    )
    (net (code "34") (name "unconnected-(J1-CSn-Pad5)") (class "Default")
      (node (ref "J1") (pin "5") (pinfunction "CSn_5") (pintype "passive+no_connect"))
    )
    (net (code "35") (name "unconnected-(J1-MISO-Pad10)") (class "Default")
      (node (ref "J1") (pin "10") (pinfunction "MISO_10") (pintype "passive+no_connect"))
    )
    (net (code "36") (name "unconnected-(J1-MOSI-Pad8)") (class "Default")
      (node (ref "J1") (pin "8") (pinfunction "MOSI_8") (pintype "passive+no_connect"))
    )
    (net (code "37") (name "unconnected-(J1-SCLK-Pad6)") (class "Default")
      (node (ref "J1") (pin "6") (pinfunction "SCLK_6") (pintype "passive+no_connect"))
    )
    (net (code "38") (name "unconnected-(S1-DNC-Pad1)") (class "Default")
      (node (ref "S1") (pin "1") (pinfunction "DNC_1") (pintype "passive+no_connect"))
    )
    (net (code "39") (name "unconnected-(S1-INT-Pad5)") (class "Default")
      (node (ref "S1") (pin "5") (pinfunction "INT_5") (pintype "passive+no_connect"))
    )
    (net (code "40") (name "unconnected-(S1-LED1-Pad9)") (class "Default")
      (node (ref "S1") (pin "9") (pinfunction "LED1_9") (pintype "passive+no_connect"))
    )
    (net (code "41") (name "unconnected-(S2-DNC-Pad1)") (class "Default")
      (node (ref "S2") (pin "1") (pinfunction "DNC_1") (pintype "passive+no_connect"))
    )
    (net (code "42") (name "unconnected-(S2-INT-Pad5)") (class "Default")
      (node (ref "S2") (pin "5") (pinfunction "INT_5") (pintype "passive+no_connect"))
    )
    (net (code "43") (name "unconnected-(S2-LED1-Pad9)") (class "Default")
      (node (ref "S2") (pin "9") (pinfunction "LED1_9") (pintype "passive+no_connect"))
    )
    (net (code "44") (name "unconnected-(S3-DNC-Pad1)") (class "Default")
      (node (ref "S3") (pin "1") (pinfunction "DNC_1") (pintype "passive+no_connect"))
    )
    (net (code "45") (name "unconnected-(S3-INT-Pad5)") (class "Default")
      (node (ref "S3") (pin "5") (pinfunction "INT_5") (pintype "passive+no_connect"))
    )
    (net (code "46") (name "unconnected-(S3-LED1-Pad9)") (class "Default")
      (node (ref "S3") (pin "9") (pinfunction "LED1_9") (pintype "passive+no_connect"))
    )
    (net (code "47") (name "unconnected-(S4-DNC-Pad1)") (class "Default")
      (node (ref "S4") (pin "1") (pinfunction "DNC_1") (pintype "passive+no_connect"))
    )
    (net (code "48") (name "unconnected-(S4-INT-Pad5)") (class "Default")
      (node (ref "S4") (pin "5") (pinfunction "INT_5") (pintype "passive+no_connect"))
    )
    (net (code "49") (name "unconnected-(S4-LED1-Pad9)") (class "Default")
      (node (ref "S4") (pin "9") (pinfunction "LED1_9") (pintype "passive+no_connect"))
    )
    (net (code "50") (name "unconnected-(S5-DNC-Pad1)") (class "Default")
      (node (ref "S5") (pin "1") (pinfunction "DNC_1") (pintype "passive+no_connect"))
    )
    (net (code "51") (name "unconnected-(S5-INT-Pad5)") (class "Default")
      (node (ref "S5") (pin "5") (pinfunction "INT_5") (pintype "passive+no_connect"))
    )
    (net (code "52") (name "unconnected-(S5-LED1-Pad9)") (class "Default")
      (node (ref "S5") (pin "9") (pinfunction "LED1_9") (pintype "passive+no_connect"))
    )
    (net (code "53") (name "unconnected-(S6-DNC-Pad1)") (class "Default")
      (node (ref "S6") (pin "1") (pinfunction "DNC_1") (pintype "passive+no_connect"))
    )
    (net (code "54") (name "unconnected-(S6-INT-Pad5)") (class "Default")
      (node (ref "S6") (pin "5") (pinfunction "INT_5") (pintype "passive+no_connect"))
    )
    (net (code "55") (name "unconnected-(S6-LED1-Pad9)") (class "Default")
      (node (ref "S6") (pin "9") (pinfunction "LED1_9") (pintype "passive+no_connect"))
    )
    (net (code "56") (name "unconnected-(U1-STAT-Pad1)") (class "Default")
      (node (ref "U1") (pin "1") (pinfunction "STAT_1") (pintype "passive+no_connect"))
    )
    (net (code "57") (name "unconnected-(U3-NC-Pad16)") (class "Default")
      (node (ref "U3") (pin "16") (pinfunction "NC_16") (pintype "passive+no_connect"))
    )
    (net (code "58") (name "unconnected-(U3-NC-Pad35)") (class "Default")
      (node (ref "U3") (pin "35") (pinfunction "NC_35") (pintype "passive+no_connect"))
    )
    (net (code "59") (name "unconnected-(U3-P0_4-Pad29)") (class "Default")
      (node (ref "U3") (pin "29") (pinfunction "P0_4_29") (pintype "passive+no_connect"))
    )
    (net (code "60") (name "unconnected-(U3-P0_5-Pad28)") (class "Default")
      (node (ref "U3") (pin "28") (pinfunction "P0_5_28") (pintype "passive+no_connect"))
    )
  )
)
